# shiftRegister.net
KiCad netlist of a schematic drawn in EAGLE
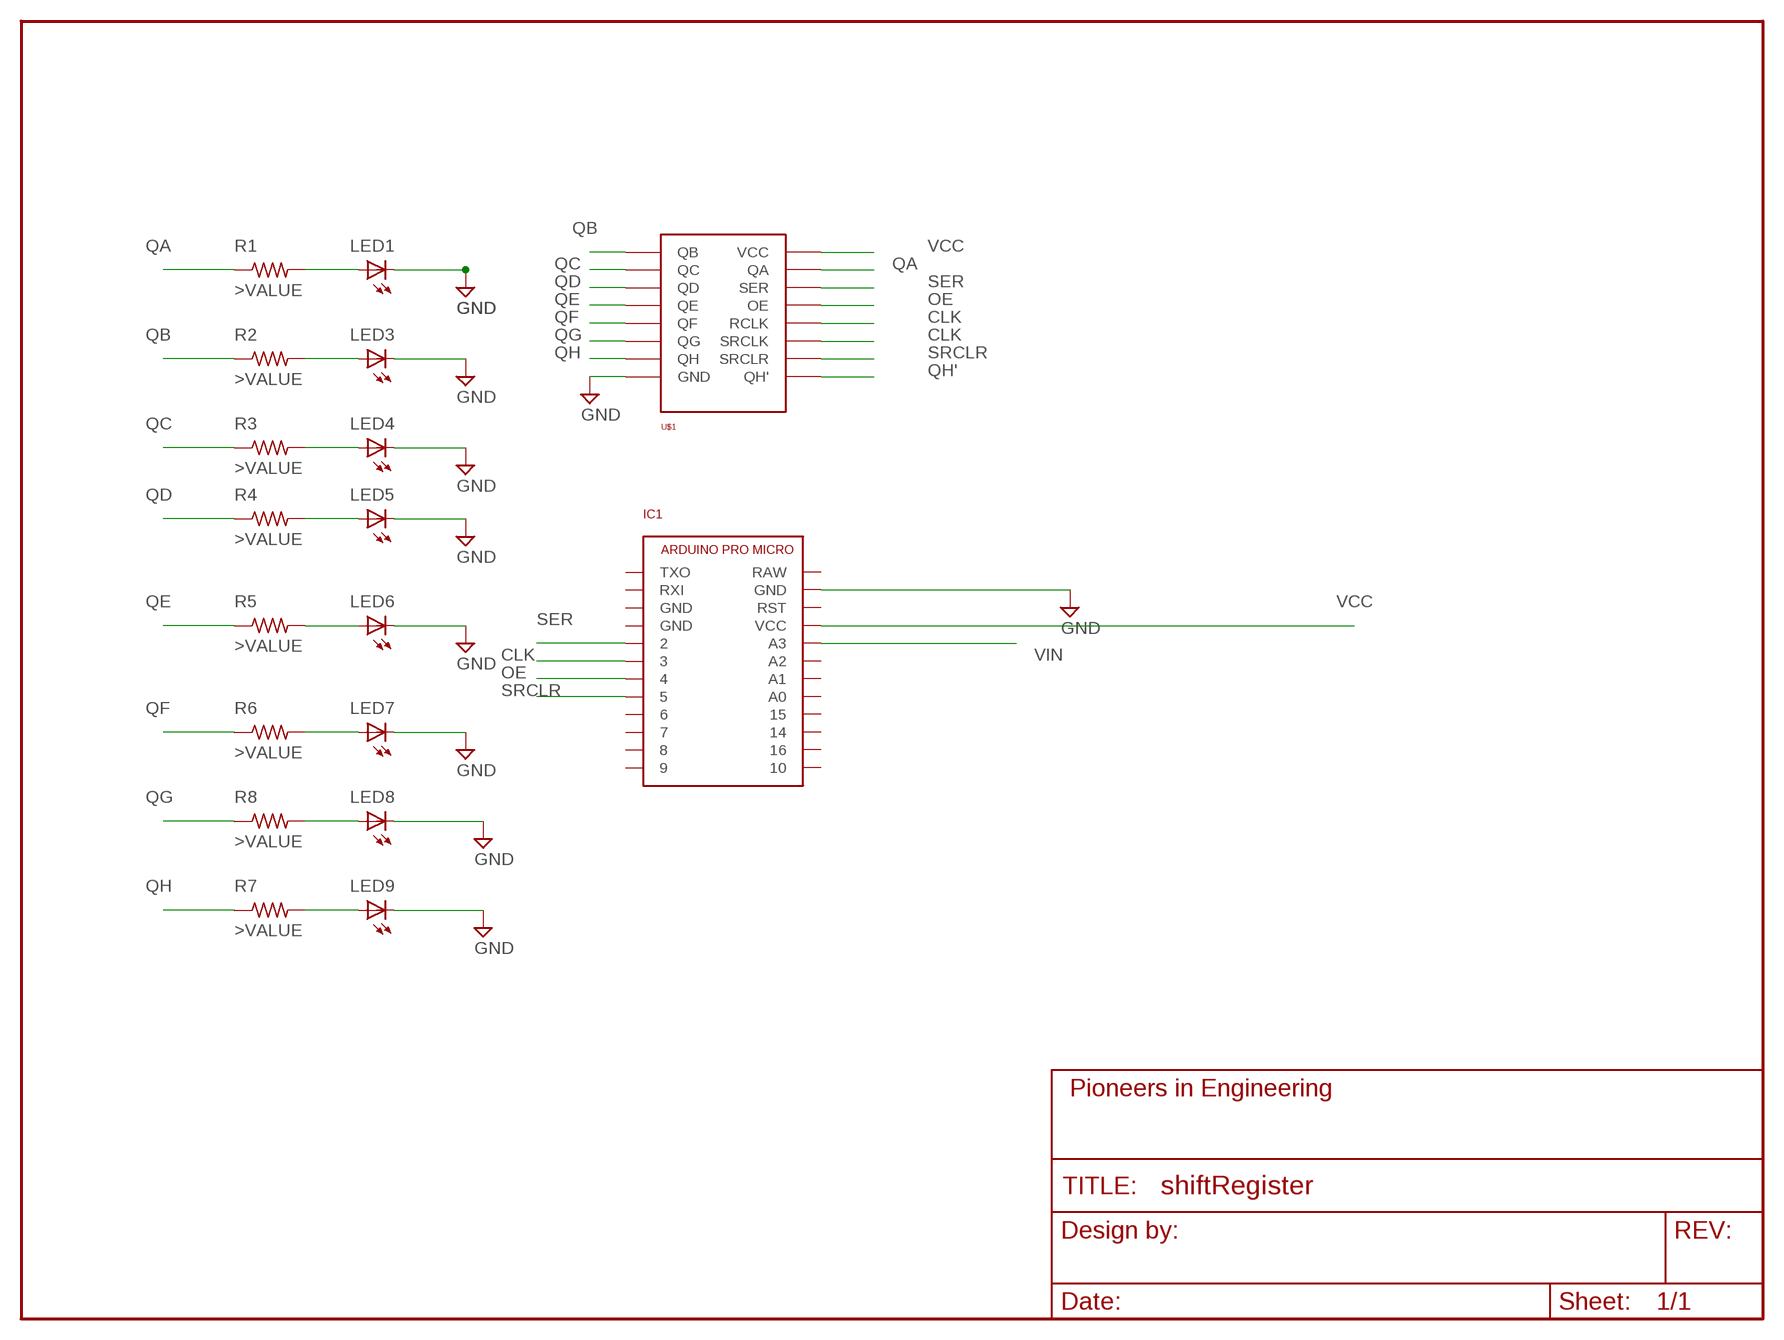
[diagram p0: schematic, sheet 1]

(export (version "E")
  (design (tool "Eeschema 10.0.6"))
  (components
    (comp (ref "IC1")
      (value "ARDUINO_PRO_MICRO")
      (footprint "eagle-import:ARDUINO_PRO_MICRO")
      (fields
        (field (name "DISTRIBUTOR_PART_NUMBER") "32284746884")
        (field (name "MANUFACTURER") "Feiyang electronics")
      )
      (libsource (lib "eagle-import") (part "ARDUINO_PRO_MICRO"))
    )
    (comp (ref "LED1")
      (value "LED-FKIT-1206")
      (footprint "eagle-import:FKIT-LED-1206")
      (libsource (lib "eagle-import") (part "LED-FKIT-1206"))
    )
    (comp (ref "LED3")
      (value "LED-FKIT-1206")
      (footprint "eagle-import:FKIT-LED-1206")
      (libsource (lib "eagle-import") (part "LED-FKIT-1206"))
    )
    (comp (ref "LED4")
      (value "LED-FKIT-1206")
      (footprint "eagle-import:FKIT-LED-1206")
      (libsource (lib "eagle-import") (part "LED-FKIT-1206"))
    )
    (comp (ref "LED5")
      (value "LED-FKIT-1206")
      (footprint "eagle-import:FKIT-LED-1206")
      (libsource (lib "eagle-import") (part "LED-FKIT-1206"))
    )
    (comp (ref "LED6")
      (value "LED-FKIT-1206")
      (footprint "eagle-import:FKIT-LED-1206")
      (libsource (lib "eagle-import") (part "LED-FKIT-1206"))
    )
    (comp (ref "LED7")
      (value "LED-FKIT-1206")
      (footprint "eagle-import:FKIT-LED-1206")
      (libsource (lib "eagle-import") (part "LED-FKIT-1206"))
    )
    (comp (ref "LED8")
      (value "LED-FKIT-1206")
      (footprint "eagle-import:FKIT-LED-1206")
      (libsource (lib "eagle-import") (part "LED-FKIT-1206"))
    )
    (comp (ref "LED9")
      (value "LED-FKIT-1206")
      (footprint "eagle-import:FKIT-LED-1206")
      (libsource (lib "eagle-import") (part "LED-FKIT-1206"))
    )
    (comp (ref "R1")
      (value ">VALUE")
      (footprint "eagle-import:R0603")
      (fields (field (name "MANUFACTURER") "Rohm Semiconductor"))
      (libsource (lib "eagle-import") (part "R-US_R0603"))
    )
    (comp (ref "R2")
      (value ">VALUE")
      (footprint "eagle-import:R0603")
      (fields (field (name "MANUFACTURER") "Rohm Semiconductor"))
      (libsource (lib "eagle-import") (part "R-US_R0603"))
    )
    (comp (ref "R3")
      (value ">VALUE")
      (footprint "eagle-import:R0603")
      (fields (field (name "MANUFACTURER") "Rohm Semiconductor"))
      (libsource (lib "eagle-import") (part "R-US_R0603"))
    )
    (comp (ref "R4")
      (value ">VALUE")
      (footprint "eagle-import:R0603")
      (fields (field (name "MANUFACTURER") "Rohm Semiconductor"))
      (libsource (lib "eagle-import") (part "R-US_R0603"))
    )
    (comp (ref "R5")
      (value ">VALUE")
      (footprint "eagle-import:R0603")
      (fields (field (name "MANUFACTURER") "Rohm Semiconductor"))
      (libsource (lib "eagle-import") (part "R-US_R0603"))
    )
    (comp (ref "R6")
      (value ">VALUE")
      (footprint "eagle-import:R0603")
      (fields (field (name "MANUFACTURER") "Rohm Semiconductor"))
      (libsource (lib "eagle-import") (part "R-US_R0603"))
    )
    (comp (ref "R7")
      (value ">VALUE")
      (footprint "eagle-import:R0603")
      (fields (field (name "MANUFACTURER") "Rohm Semiconductor"))
      (libsource (lib "eagle-import") (part "R-US_R0603"))
    )
    (comp (ref "R8")
      (value ">VALUE")
      (footprint "eagle-import:R0603")
      (fields (field (name "MANUFACTURER") "Rohm Semiconductor"))
      (libsource (lib "eagle-import") (part "R-US_R0603"))
    )
    (comp (ref "U$1")
      (value "SN74HC595")
      (footprint "eagle-import:SN74HC595")
      (libsource (lib "eagle-import") (part "SN74HC595"))
    )
  )
  (nets
    (net (code "1") (name "/CLK") (class "Default")
      (node (ref "IC1") (pin "3") (pinfunction "3_3") (pintype "bidirectional"))
      (node (ref "U$1") (pin "RCLK") (pinfunction "RCLK_RCLK") (pintype "bidirectional"))
      (node (ref "U$1") (pin "SRCLK") (pinfunction "SRCLK_SRCLK") (pintype "bidirectional"))
    )
    (net (code "2") (name "/OE") (class "Default")
      (node (ref "IC1") (pin "4") (pinfunction "4_4") (pintype "bidirectional"))
      (node (ref "U$1") (pin "OE") (pinfunction "OE_OE") (pintype "bidirectional"))
    )
    (net (code "3") (name "/QA") (class "Default")
      (node (ref "R1") (pin "1") (pinfunction "1_1") (pintype "passive"))
      (node (ref "U$1") (pin "QA") (pinfunction "QA_QA") (pintype "bidirectional"))
    )
    (net (code "4") (name "/QB") (class "Default")
      (node (ref "R2") (pin "1") (pinfunction "1_1") (pintype "passive"))
      (node (ref "U$1") (pin "QB") (pinfunction "QB_QB") (pintype "bidirectional"))
    )
    (net (code "5") (name "/QC") (class "Default")
      (node (ref "R3") (pin "1") (pinfunction "1_1") (pintype "passive"))
      (node (ref "U$1") (pin "QC") (pinfunction "QC_QC") (pintype "bidirectional"))
    )
    (net (code "6") (name "/QD") (class "Default")
      (node (ref "R4") (pin "1") (pinfunction "1_1") (pintype "passive"))
      (node (ref "U$1") (pin "QD") (pinfunction "QD_QD") (pintype "bidirectional"))
    )
    (net (code "7") (name "/QE") (class "Default")
      (node (ref "R5") (pin "1") (pinfunction "1_1") (pintype "passive"))
      (node (ref "U$1") (pin "QE") (pinfunction "QE_QE") (pintype "bidirectional"))
    )
    (net (code "8") (name "/QF") (class "Default")
      (node (ref "R6") (pin "1") (pinfunction "1_1") (pintype "passive"))
      (node (ref "U$1") (pin "QF") (pinfunction "QF_QF") (pintype "bidirectional"))
    )
    (net (code "9") (name "/QG") (class "Default")
      (node (ref "R8") (pin "1") (pinfunction "1_1") (pintype "passive"))
      (node (ref "U$1") (pin "QG") (pinfunction "QG_QG") (pintype "bidirectional"))
    )
    (net (code "10") (name "/QH") (class "Default")
      (node (ref "R7") (pin "1") (pinfunction "1_1") (pintype "passive"))
      (node (ref "U$1") (pin "QH") (pinfunction "QH_QH") (pintype "bidirectional"))
    )
    (net (code "11") (name "/QH'") (class "Default")
      (node (ref "U$1") (pin "QH'") (pinfunction "QH'_QH'") (pintype "bidirectional"))
    )
    (net (code "12") (name "/SER") (class "Default")
      (node (ref "IC1") (pin "2") (pinfunction "2_2") (pintype "bidirectional"))
      (node (ref "U$1") (pin "SER") (pinfunction "SER_SER") (pintype "bidirectional"))
    )
    (net (code "13") (name "/SRCLR") (class "Default")
      (node (ref "IC1") (pin "5") (pinfunction "5_5") (pintype "bidirectional"))
      (node (ref "U$1") (pin "SRCLR") (pinfunction "SRCLR_SRCLR") (pintype "bidirectional"))
    )
    (net (code "14") (name "/VCC") (class "Default")
      (node (ref "IC1") (pin "VCC") (pinfunction "VCC_VCC") (pintype "bidirectional"))
      (node (ref "U$1") (pin "VCC") (pinfunction "VCC_VCC") (pintype "bidirectional"))
    )
    (net (code "15") (name "/VIN") (class "Default")
      (node (ref "IC1") (pin "A3") (pinfunction "A3_A3") (pintype "bidirectional"))
    )
    (net (code "16") (name "GND") (class "Default")
      (node (ref "IC1") (pin "GND@2") (pinfunction "GND_GND@2") (pintype "bidirectional"))
      (node (ref "LED1") (pin "C") (pinfunction "C_C") (pintype "passive"))
      (node (ref "LED3") (pin "C") (pinfunction "C_C") (pintype "passive"))
      (node (ref "LED4") (pin "C") (pinfunction "C_C") (pintype "passive"))
      (node (ref "LED5") (pin "C") (pinfunction "C_C") (pintype "passive"))
      (node (ref "LED6") (pin "C") (pinfunction "C_C") (pintype "passive"))
      (node (ref "LED7") (pin "C") (pinfunction "C_C") (pintype "passive"))
      (node (ref "LED8") (pin "C") (pinfunction "C_C") (pintype "passive"))
      (node (ref "LED9") (pin "C") (pinfunction "C_C") (pintype "passive"))
      (node (ref "U$1") (pin "GND") (pinfunction "GND_GND") (pintype "bidirectional"))
    )
    (net (code "17") (name "Net-(LED1-PadA)") (class "Default")
      (node (ref "LED1") (pin "A") (pinfunction "A_A") (pintype "passive"))
      (node (ref "R1") (pin "2") (pinfunction "2_2") (pintype "passive"))
    )
    (net (code "18") (name "Net-(LED3-PadA)") (class "Default")
      (node (ref "LED3") (pin "A") (pinfunction "A_A") (pintype "passive"))
      (node (ref "R2") (pin "2") (pinfunction "2_2") (pintype "passive"))
    )
    (net (code "19") (name "Net-(LED4-PadA)") (class "Default")
      (node (ref "LED4") (pin "A") (pinfunction "A_A") (pintype "passive"))
      (node (ref "R3") (pin "2") (pinfunction "2_2") (pintype "passive"))
    )
    (net (code "20") (name "Net-(LED5-PadA)") (class "Default")
      (node (ref "LED5") (pin "A") (pinfunction "A_A") (pintype "passive"))
      (node (ref "R4") (pin "2") (pinfunction "2_2") (pintype "passive"))
    )
    (net (code "21") (name "Net-(LED6-PadA)") (class "Default")
      (node (ref "LED6") (pin "A") (pinfunction "A_A") (pintype "passive"))
      (node (ref "R5") (pin "2") (pinfunction "2_2") (pintype "passive"))
    )
    (net (code "22") (name "Net-(LED7-PadA)") (class "Default")
      (node (ref "LED7") (pin "A") (pinfunction "A_A") (pintype "passive"))
      (node (ref "R6") (pin "2") (pinfunction "2_2") (pintype "passive"))
    )
    (net (code "23") (name "Net-(LED8-PadA)") (class "Default")
      (node (ref "LED8") (pin "A") (pinfunction "A_A") (pintype "passive"))
      (node (ref "R8") (pin "2") (pinfunction "2_2") (pintype "passive"))
    )
    (net (code "24") (name "Net-(LED9-PadA)") (class "Default")
      (node (ref "LED9") (pin "A") (pinfunction "A_A") (pintype "passive"))
      (node (ref "R7") (pin "2") (pinfunction "2_2") (pintype "passive"))
    )
    (net (code "25") (name "unconnected-(IC1-GND-PadGND@0)") (class "Default")
      (node (ref "IC1") (pin "GND@0") (pinfunction "GND_GND@0") (pintype "bidirectional"))
    )
    (net (code "26") (name "unconnected-(IC1-GND-PadGND@1)") (class "Default")
      (node (ref "IC1") (pin "GND@1") (pinfunction "GND_GND@1") (pintype "bidirectional"))
    )
    (net (code "27") (name "unconnected-(IC1-Pad6)") (class "Default")
      (node (ref "IC1") (pin "6") (pinfunction "6_6") (pintype "bidirectional"))
    )
    (net (code "28") (name "unconnected-(IC1-Pad7)") (class "Default")
      (node (ref "IC1") (pin "7") (pinfunction "7_7") (pintype "bidirectional"))
    )
    (net (code "29") (name "unconnected-(IC1-Pad8)") (class "Default")
      (node (ref "IC1") (pin "8") (pinfunction "8_8") (pintype "bidirectional"))
    )
    (net (code "30") (name "unconnected-(IC1-Pad9)") (class "Default")
      (node (ref "IC1") (pin "9") (pinfunction "9_9") (pintype "bidirectional"))
    )
    (net (code "31") (name "unconnected-(IC1-Pad10)") (class "Default")
      (node (ref "IC1") (pin "10") (pinfunction "10_10") (pintype "bidirectional"))
    )
    (net (code "32") (name "unconnected-(IC1-Pad14)") (class "Default")
      (node (ref "IC1") (pin "14") (pinfunction "14_14") (pintype "bidirectional"))
    )
    (net (code "33") (name "unconnected-(IC1-Pad15)") (class "Default")
      (node (ref "IC1") (pin "15") (pinfunction "15_15") (pintype "bidirectional"))
    )
    (net (code "34") (name "unconnected-(IC1-Pad16)") (class "Default")
      (node (ref "IC1") (pin "16") (pinfunction "16_16") (pintype "bidirectional"))
    )
    (net (code "35") (name "unconnected-(IC1-PadA0)") (class "Default")
      (node (ref "IC1") (pin "A0") (pinfunction "A0_A0") (pintype "bidirectional"))
    )
    (net (code "36") (name "unconnected-(IC1-PadA1)") (class "Default")
      (node (ref "IC1") (pin "A1") (pinfunction "A1_A1") (pintype "bidirectional"))
    )
    (net (code "37") (name "unconnected-(IC1-PadA2)") (class "Default")
      (node (ref "IC1") (pin "A2") (pinfunction "A2_A2") (pintype "bidirectional"))
    )
    (net (code "38") (name "unconnected-(IC1-PadRAW)") (class "Default")
      (node (ref "IC1") (pin "RAW") (pinfunction "RAW_RAW") (pintype "bidirectional"))
    )
    (net (code "39") (name "unconnected-(IC1-PadRST)") (class "Default")
      (node (ref "IC1") (pin "RST") (pinfunction "RST_RST") (pintype "bidirectional"))
    )
    (net (code "40") (name "unconnected-(IC1-PadRXI)") (class "Default")
      (node (ref "IC1") (pin "RXI") (pinfunction "RXI_RXI") (pintype "bidirectional"))
    )
    (net (code "41") (name "unconnected-(IC1-PadTXO)") (class "Default")
      (node (ref "IC1") (pin "TXO") (pinfunction "TXO_TXO") (pintype "bidirectional"))
    )
  )
)
